# Plinto-Rev_02.net
KiCad netlist of a schematic drawn in EAGLE
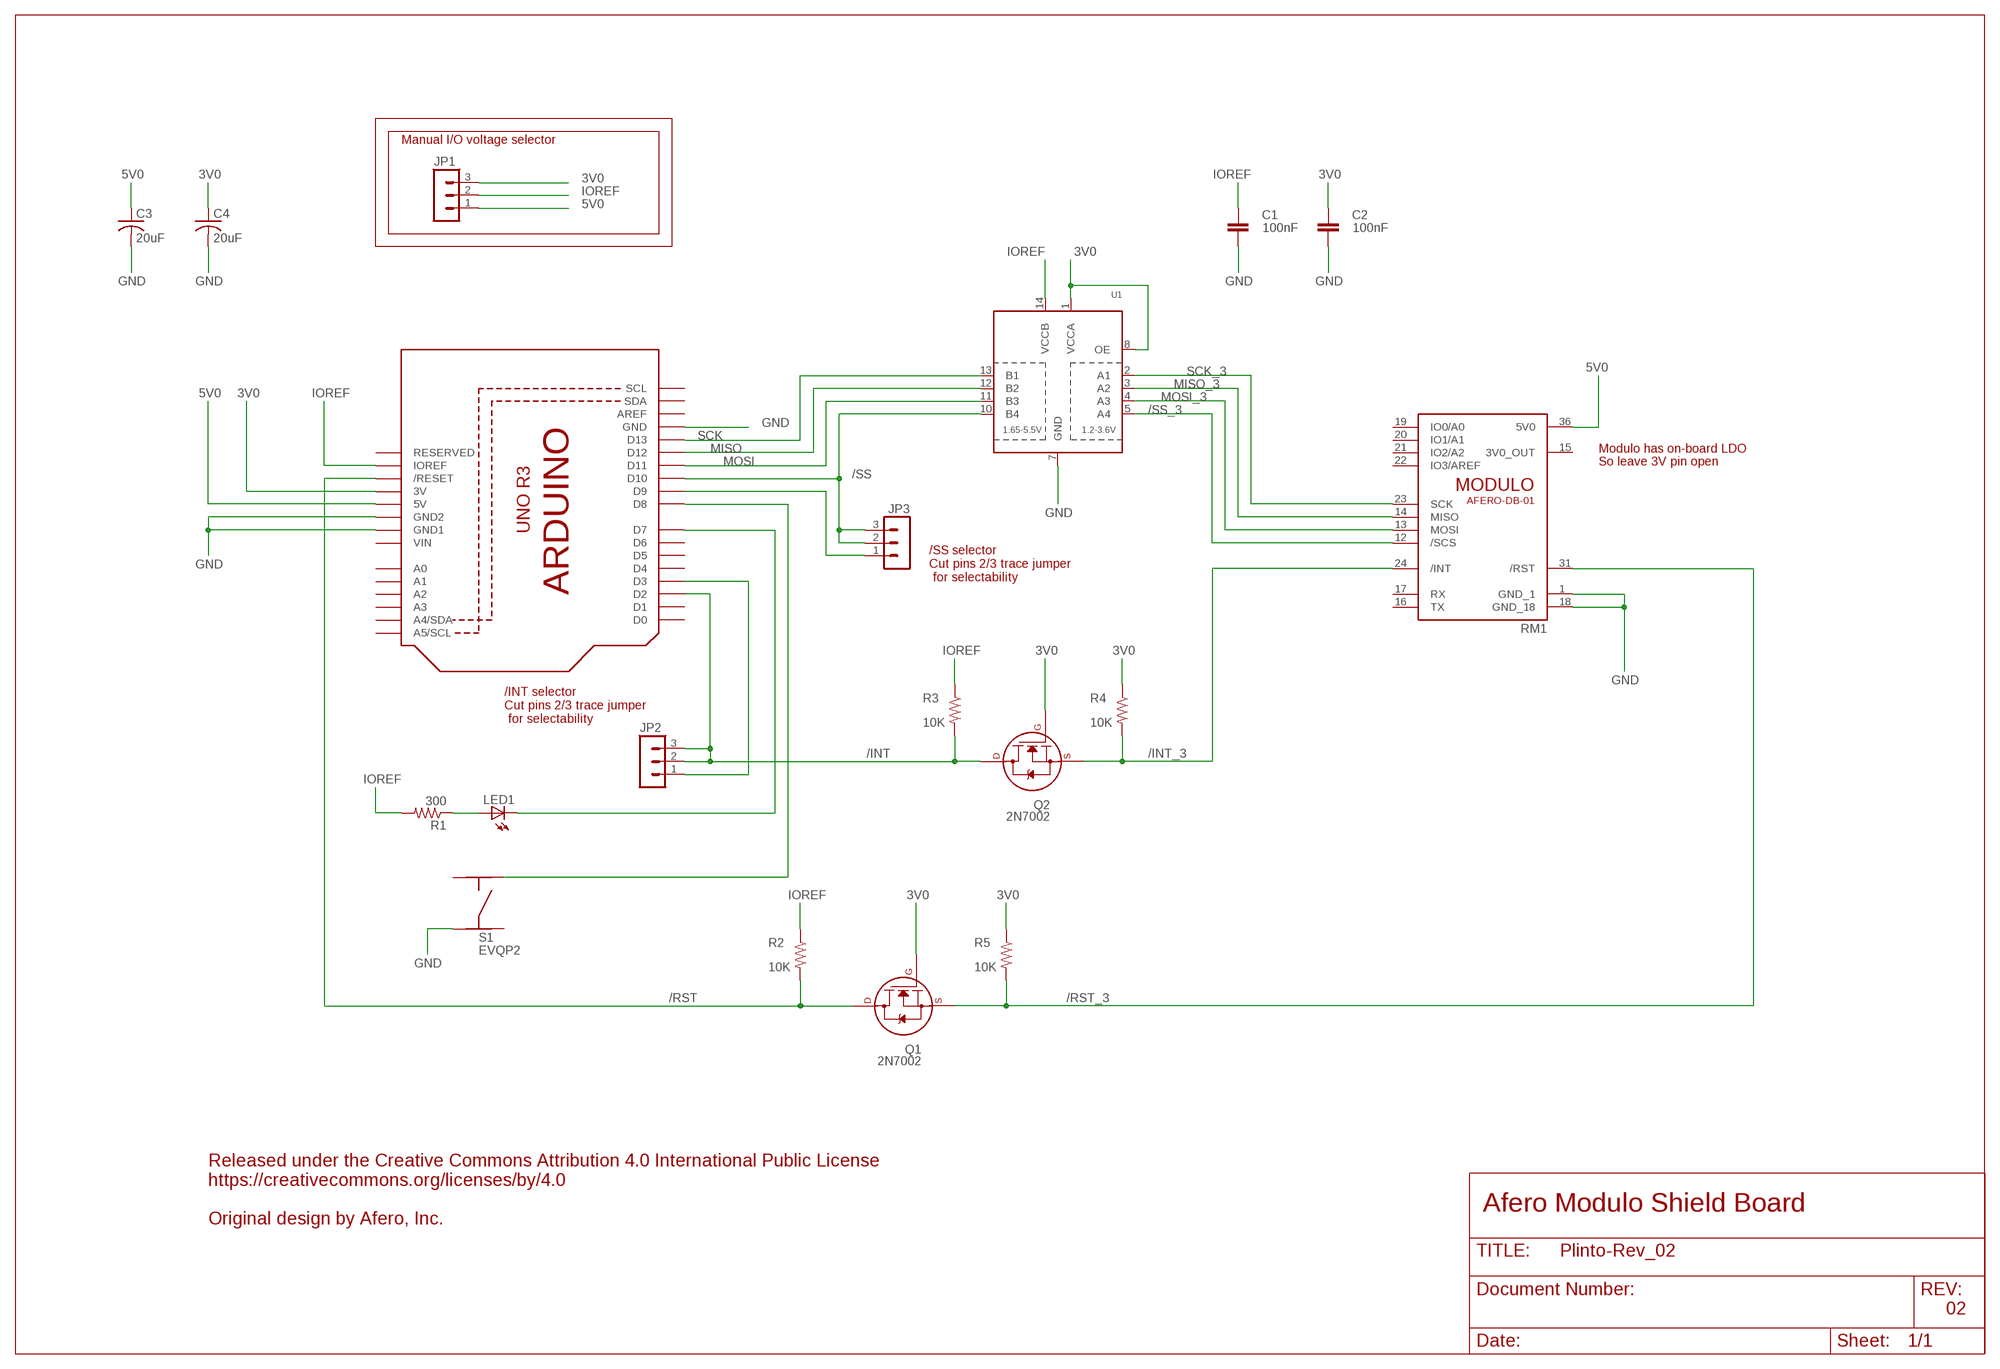
[diagram p0: schematic, sheet 1]

(export (version "E")
  (design (tool "Eeschema 10.0.6"))
  (components
    (comp (ref "C1")
      (value "100nF")
      (footprint "eagle-import:C0402")
      (libsource (lib "eagle-import") (part "C-EUC0402"))
    )
    (comp (ref "C2")
      (value "100nF")
      (footprint "eagle-import:C0402")
      (libsource (lib "eagle-import") (part "C-EUC0402"))
    )
    (comp (ref "C3")
      (value "20uF")
      (footprint "eagle-import:C0805")
      (libsource (lib "eagle-import") (part "C-USC0805"))
    )
    (comp (ref "C4")
      (value "20uF")
      (footprint "eagle-import:C0805")
      (libsource (lib "eagle-import") (part "C-USC0805"))
    )
    (comp (ref "JP1")
      (value "3PIN_JMPR")
      (footprint "eagle-import:3PIN_JMPR")
      (libsource (lib "eagle-import") (part "3PIN_JMPR"))
    )
    (comp (ref "JP2")
      (value "3PIN_JMPR")
      (footprint "eagle-import:3PIN_JMPR")
      (libsource (lib "eagle-import") (part "3PIN_JMPR"))
    )
    (comp (ref "JP3")
      (value "3PIN_JMPR")
      (footprint "eagle-import:3PIN_JMPR")
      (libsource (lib "eagle-import") (part "3PIN_JMPR"))
    )
    (comp (ref "LED1")
      (value "LEDCHIPLED_0603")
      (footprint "eagle-import:CHIPLED_0603")
      (libsource (lib "eagle-import") (part "LEDCHIPLED_0603"))
    )
    (comp (ref "Q1")
      (value "2N7002")
      (footprint "eagle-import:SOT-23")
      (libsource (lib "eagle-import") (part "2N700_SOT232"))
    )
    (comp (ref "Q2")
      (value "2N7002")
      (footprint "eagle-import:SOT-23")
      (libsource (lib "eagle-import") (part "2N700_SOT232"))
    )
    (comp (ref "R1")
      (value "300")
      (footprint "eagle-import:R0402")
      (libsource (lib "eagle-import") (part "R-US_R0402"))
    )
    (comp (ref "R2")
      (value "10K")
      (footprint "eagle-import:R0402")
      (libsource (lib "eagle-import") (part "R-US_R0402"))
    )
    (comp (ref "R3")
      (value "10K")
      (footprint "eagle-import:R0402")
      (libsource (lib "eagle-import") (part "R-US_R0402"))
    )
    (comp (ref "R4")
      (value "10K")
      (footprint "eagle-import:R0402")
      (libsource (lib "eagle-import") (part "R-US_R0402"))
    )
    (comp (ref "R5")
      (value "10K")
      (footprint "eagle-import:R0402")
      (libsource (lib "eagle-import") (part "R-US_R0402"))
    )
    (comp (ref "RM1")
      (value "MODULOAFERO-DB-01")
      (footprint "eagle-import:MODULO")
      (libsource (lib "eagle-import") (part "MODULOAFERO-DB-01"))
    )
    (comp (ref "S1")
      (value "EVQP2")
      (footprint "eagle-import:EVQP2")
      (libsource (lib "eagle-import") (part "EVQP2"))
    )
    (comp (ref "U$1")
      (value "ARDUINO_UNO_R3KIBANVERSION")
      (footprint "eagle-import:ARDUINO_R3")
      (libsource (lib "eagle-import") (part "ARDUINO_UNO_R3KIBANVERSION"))
    )
    (comp (ref "U1")
      (value "TXB0104PWR")
      (footprint "eagle-import:TSSOP14")
      (libsource (lib "eagle-import") (part "TXB0104PWR"))
    )
  )
  (nets
    (net (code "1") (name "/3V0") (class "Default")
      (node (ref "C2") (pin "1") (pinfunction "1_1") (pintype "passive"))
      (node (ref "C4") (pin "1") (pinfunction "1_1") (pintype "passive"))
      (node (ref "JP1") (pin "3") (pinfunction "3_3") (pintype "passive"))
      (node (ref "Q1") (pin "1") (pinfunction "G_1") (pintype "tri_state"))
      (node (ref "Q2") (pin "1") (pinfunction "G_1") (pintype "tri_state"))
      (node (ref "R4") (pin "1") (pinfunction "1_1") (pintype "passive"))
      (node (ref "R5") (pin "1") (pinfunction "1_1") (pintype "passive"))
      (node (ref "U$1") (pin "3V") (pinfunction "3V_3V") (pintype "power_in"))
      (node (ref "U1") (pin "1") (pinfunction "VCCA_1") (pintype "bidirectional"))
      (node (ref "U1") (pin "8") (pinfunction "OE_8") (pintype "bidirectional"))
    )
    (net (code "2") (name "/3V0_OUT") (class "Default")
      (node (ref "RM1") (pin "15") (pinfunction "3V0_OUT_15") (pintype "power_in"))
    )
    (net (code "3") (name "/5V0") (class "Default")
      (node (ref "C3") (pin "1") (pinfunction "1_1") (pintype "passive"))
      (node (ref "JP1") (pin "1") (pinfunction "1_1") (pintype "passive"))
      (node (ref "RM1") (pin "36") (pinfunction "5V0_36") (pintype "power_in"))
      (node (ref "U$1") (pin "5V") (pinfunction "5V_5V") (pintype "power_in"))
    )
    (net (code "4") (name "/GND") (class "Default")
      (node (ref "C1") (pin "2") (pinfunction "2_2") (pintype "passive"))
      (node (ref "C2") (pin "2") (pinfunction "2_2") (pintype "passive"))
      (node (ref "C3") (pin "2") (pinfunction "2_2") (pintype "passive"))
      (node (ref "C4") (pin "2") (pinfunction "2_2") (pintype "passive"))
      (node (ref "RM1") (pin "1") (pinfunction "GND_1_1") (pintype "power_in"))
      (node (ref "RM1") (pin "18") (pinfunction "GND_18_18") (pintype "power_in"))
      (node (ref "S1") (pin "P$4") (pinfunction "P$4_P$4") (pintype "passive"))
      (node (ref "U$1") (pin "GND") (pinfunction "GND_GND") (pintype "power_in"))
      (node (ref "U$1") (pin "GND1") (pinfunction "GND1_GND1") (pintype "power_in"))
      (node (ref "U$1") (pin "GND2") (pinfunction "GND2_GND2") (pintype "power_in"))
      (node (ref "U1") (pin "7") (pinfunction "GND_7") (pintype "bidirectional"))
    )
    (net (code "5") (name "/IOREF") (class "Default")
      (node (ref "C1") (pin "1") (pinfunction "1_1") (pintype "passive"))
      (node (ref "JP1") (pin "2") (pinfunction "2_2") (pintype "passive"))
      (node (ref "R1") (pin "2") (pinfunction "2_2") (pintype "passive"))
      (node (ref "R2") (pin "1") (pinfunction "1_1") (pintype "passive"))
      (node (ref "R3") (pin "1") (pinfunction "1_1") (pintype "passive"))
      (node (ref "U$1") (pin "IOREF") (pinfunction "IOREF_IOREF") (pintype "output"))
      (node (ref "U1") (pin "14") (pinfunction "VCCB_14") (pintype "bidirectional"))
    )
    (net (code "6") (name "/MISO") (class "Default")
      (node (ref "U$1") (pin "D12") (pinfunction "D12_D12") (pintype "bidirectional"))
      (node (ref "U1") (pin "12") (pinfunction "B2_12") (pintype "bidirectional"))
    )
    (net (code "7") (name "/MISO_3") (class "Default")
      (node (ref "RM1") (pin "14") (pinfunction "MISO_14") (pintype "bidirectional"))
      (node (ref "U1") (pin "3") (pinfunction "A2_3") (pintype "bidirectional"))
    )
    (net (code "8") (name "/MOSI") (class "Default")
      (node (ref "U$1") (pin "D11") (pinfunction "D11_D11") (pintype "bidirectional"))
      (node (ref "U1") (pin "11") (pinfunction "B3_11") (pintype "bidirectional"))
    )
    (net (code "9") (name "/MOSI_3") (class "Default")
      (node (ref "RM1") (pin "13") (pinfunction "MOSI_13") (pintype "bidirectional"))
      (node (ref "U1") (pin "4") (pinfunction "A3_4") (pintype "bidirectional"))
    )
    (net (code "10") (name "/SCK") (class "Default")
      (node (ref "U$1") (pin "D13") (pinfunction "D13_D13") (pintype "bidirectional"))
      (node (ref "U1") (pin "13") (pinfunction "B1_13") (pintype "bidirectional"))
    )
    (net (code "11") (name "/SCK_3") (class "Default")
      (node (ref "RM1") (pin "23") (pinfunction "SCK_23") (pintype "bidirectional"))
      (node (ref "U1") (pin "2") (pinfunction "A1_2") (pintype "bidirectional"))
    )
    (net (code "12") (name "/VIN") (class "Default")
      (node (ref "U$1") (pin "VIN") (pinfunction "VIN_VIN") (pintype "power_in"))
    )
    (net (code "13") (name "/{slash}INT") (class "Default")
      (node (ref "JP2") (pin "2") (pinfunction "2_2") (pintype "passive"))
      (node (ref "JP2") (pin "3") (pinfunction "3_3") (pintype "passive"))
      (node (ref "Q2") (pin "3") (pinfunction "D_3") (pintype "bidirectional"))
      (node (ref "R3") (pin "2") (pinfunction "2_2") (pintype "passive"))
      (node (ref "U$1") (pin "D2") (pinfunction "D2_D2") (pintype "bidirectional"))
    )
    (net (code "14") (name "/{slash}INT_3") (class "Default")
      (node (ref "Q2") (pin "2") (pinfunction "S_2") (pintype "bidirectional"))
      (node (ref "R4") (pin "2") (pinfunction "2_2") (pintype "passive"))
      (node (ref "RM1") (pin "24") (pinfunction "/INT_24") (pintype "bidirectional"))
    )
    (net (code "15") (name "/{slash}RST") (class "Default")
      (node (ref "Q1") (pin "3") (pinfunction "D_3") (pintype "bidirectional"))
      (node (ref "R2") (pin "2") (pinfunction "2_2") (pintype "passive"))
      (node (ref "U$1") (pin "RESET") (pinfunction "/RESET_RESET") (pintype "bidirectional"))
    )
    (net (code "16") (name "/{slash}RST_3") (class "Default")
      (node (ref "Q1") (pin "2") (pinfunction "S_2") (pintype "bidirectional"))
      (node (ref "R5") (pin "2") (pinfunction "2_2") (pintype "passive"))
      (node (ref "RM1") (pin "31") (pinfunction "/RST_31") (pintype "input"))
    )
    (net (code "17") (name "/{slash}SS") (class "Default")
      (node (ref "JP3") (pin "2") (pinfunction "2_2") (pintype "passive"))
      (node (ref "JP3") (pin "3") (pinfunction "3_3") (pintype "passive"))
      (node (ref "U$1") (pin "D10") (pinfunction "D10_D10") (pintype "bidirectional"))
      (node (ref "U1") (pin "10") (pinfunction "B4_10") (pintype "bidirectional"))
    )
    (net (code "18") (name "/{slash}SS_3") (class "Default")
      (node (ref "RM1") (pin "12") (pinfunction "/SCS_12") (pintype "bidirectional"))
      (node (ref "U1") (pin "5") (pinfunction "A4_5") (pintype "bidirectional"))
    )
    (net (code "19") (name "Net-(JP2-Pad1)") (class "Default")
      (node (ref "JP2") (pin "1") (pinfunction "1_1") (pintype "passive"))
      (node (ref "U$1") (pin "D3") (pinfunction "D3_D3") (pintype "bidirectional"))
    )
    (net (code "20") (name "Net-(JP3-Pad1)") (class "Default")
      (node (ref "JP3") (pin "1") (pinfunction "1_1") (pintype "passive"))
      (node (ref "U$1") (pin "D9") (pinfunction "D9_D9") (pintype "bidirectional"))
    )
    (net (code "21") (name "Net-(LED1-PadA)") (class "Default")
      (node (ref "LED1") (pin "A") (pinfunction "A_A") (pintype "passive"))
      (node (ref "R1") (pin "1") (pinfunction "1_1") (pintype "passive"))
    )
    (net (code "22") (name "Net-(LED1-PadC)") (class "Default")
      (node (ref "LED1") (pin "C") (pinfunction "C_C") (pintype "passive"))
      (node (ref "U$1") (pin "D7") (pinfunction "D7_D7") (pintype "bidirectional"))
    )
    (net (code "23") (name "Net-(S1-PadP$1)") (class "Default")
      (node (ref "S1") (pin "P$1") (pinfunction "P$1_P$1") (pintype "passive"))
      (node (ref "U$1") (pin "D8") (pinfunction "D8_D8") (pintype "bidirectional"))
    )
    (net (code "24") (name "unconnected-(RM1-IO0{slash}A0-Pad19)") (class "Default")
      (node (ref "RM1") (pin "19") (pinfunction "IO0/A0_19") (pintype "bidirectional"))
    )
    (net (code "25") (name "unconnected-(RM1-IO1{slash}A1-Pad20)") (class "Default")
      (node (ref "RM1") (pin "20") (pinfunction "IO1/A1_20") (pintype "bidirectional"))
    )
    (net (code "26") (name "unconnected-(RM1-IO2{slash}A2-Pad21)") (class "Default")
      (node (ref "RM1") (pin "21") (pinfunction "IO2/A2_21") (pintype "bidirectional"))
    )
    (net (code "27") (name "unconnected-(RM1-IO3{slash}AREF-Pad22)") (class "Default")
      (node (ref "RM1") (pin "22") (pinfunction "IO3/AREF_22") (pintype "bidirectional"))
    )
    (net (code "28") (name "unconnected-(RM1-RX-Pad17)") (class "Default")
      (node (ref "RM1") (pin "17") (pinfunction "RX_17") (pintype "bidirectional"))
    )
    (net (code "29") (name "unconnected-(RM1-TX-Pad16)") (class "Default")
      (node (ref "RM1") (pin "16") (pinfunction "TX_16") (pintype "bidirectional"))
    )
    (net (code "30") (name "unconnected-(S1-PadP$2)") (class "Default")
      (node (ref "S1") (pin "P$2") (pinfunction "P$2_P$2") (pintype "passive"))
    )
    (net (code "31") (name "unconnected-(S1-PadP$3)") (class "Default")
      (node (ref "S1") (pin "P$3") (pinfunction "P$3_P$3") (pintype "passive"))
    )
    (net (code "32") (name "unconnected-(U$1-A4{slash}SDA-PadA4)") (class "Default")
      (node (ref "U$1") (pin "A4") (pinfunction "A4/SDA_A4") (pintype "bidirectional"))
    )
    (net (code "33") (name "unconnected-(U$1-A5{slash}SCL-PadA5)") (class "Default")
      (node (ref "U$1") (pin "A5") (pinfunction "A5/SCL_A5") (pintype "bidirectional"))
    )
    (net (code "34") (name "unconnected-(U$1-PadA0)") (class "Default")
      (node (ref "U$1") (pin "A0") (pinfunction "A0_A0") (pintype "bidirectional"))
    )
    (net (code "35") (name "unconnected-(U$1-PadA1)") (class "Default")
      (node (ref "U$1") (pin "A1") (pinfunction "A1_A1") (pintype "bidirectional"))
    )
    (net (code "36") (name "unconnected-(U$1-PadA2)") (class "Default")
      (node (ref "U$1") (pin "A2") (pinfunction "A2_A2") (pintype "bidirectional"))
    )
    (net (code "37") (name "unconnected-(U$1-PadA3)") (class "Default")
      (node (ref "U$1") (pin "A3") (pinfunction "A3_A3") (pintype "bidirectional"))
    )
    (net (code "38") (name "unconnected-(U$1-PadAREF)") (class "Default")
      (node (ref "U$1") (pin "AREF") (pinfunction "AREF_AREF") (pintype "bidirectional"))
    )
    (net (code "39") (name "unconnected-(U$1-PadD0)") (class "Default")
      (node (ref "U$1") (pin "D0") (pinfunction "D0_D0") (pintype "bidirectional"))
    )
    (net (code "40") (name "unconnected-(U$1-PadD1)") (class "Default")
      (node (ref "U$1") (pin "D1") (pinfunction "D1_D1") (pintype "bidirectional"))
    )
    (net (code "41") (name "unconnected-(U$1-PadD4)") (class "Default")
      (node (ref "U$1") (pin "D4") (pinfunction "D4_D4") (pintype "bidirectional"))
    )
    (net (code "42") (name "unconnected-(U$1-PadD5)") (class "Default")
      (node (ref "U$1") (pin "D5") (pinfunction "D5_D5") (pintype "bidirectional"))
    )
    (net (code "43") (name "unconnected-(U$1-PadD6)") (class "Default")
      (node (ref "U$1") (pin "D6") (pinfunction "D6_D6") (pintype "bidirectional"))
    )
    (net (code "44") (name "unconnected-(U$1-PadRESERVED)") (class "Default")
      (node (ref "U$1") (pin "RESERVED") (pinfunction "RESERVED_RESERVED") (pintype "no_connect"))
    )
    (net (code "45") (name "unconnected-(U$1-PadSCL)") (class "Default")
      (node (ref "U$1") (pin "SCL") (pinfunction "SCL_SCL") (pintype "bidirectional"))
    )
    (net (code "46") (name "unconnected-(U$1-PadSDA)") (class "Default")
      (node (ref "U$1") (pin "SDA") (pinfunction "SDA_SDA") (pintype "bidirectional"))
    )
  )
)
